# Sheet1.net
KiCad netlist of a schematic drawn in Altium Designer
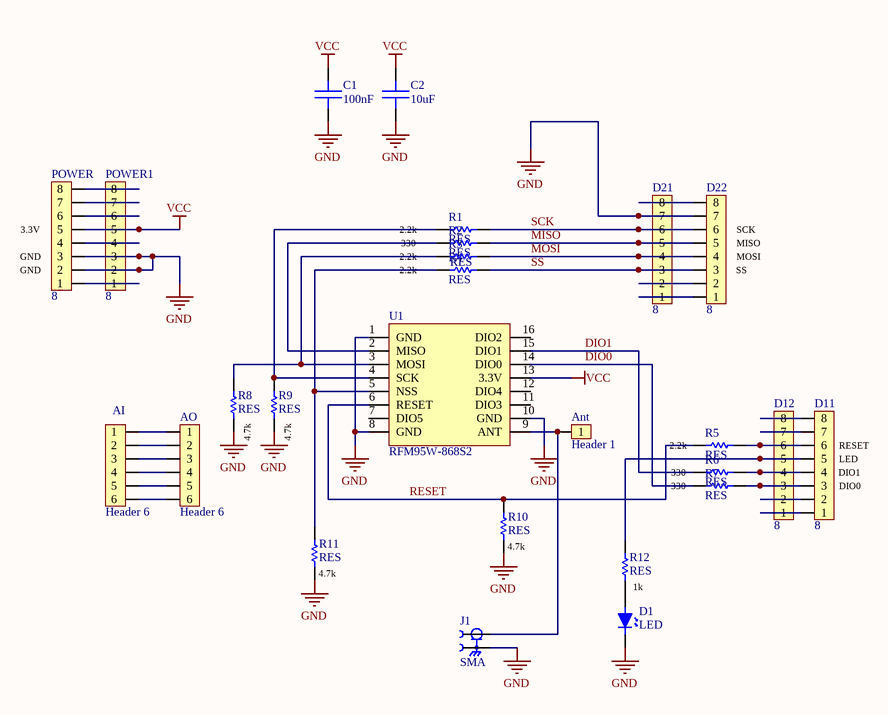
[diagram p0: Sheet1.SchDoc]

(export (version "E")
  (design (tool "Eeschema 10.0.6"))
  (components
    (comp (ref "AI")
      (value "Header 6")
      (footprint "PH-1X6")
      (description "PIN HEADER 1x6 2.56mm")
      (libsource (lib "") (part "PH-1X6_1"))
    )
    (comp (ref "Ant")
      (value "Header 1")
      (footprint "PH-1X1")
      (description "PIN HEADER 1x1 2.56mm")
      (libsource (lib "IOElectro") (part "PH-1X1"))
    )
    (comp (ref "AO")
      (value "Header 6")
      (footprint "PH-1X6")
      (description "PIN HEADER 1x6 2.56mm")
      (libsource (lib "IOElectro") (part "PH-1X6"))
    )
    (comp (ref "C1")
      (value "100nF")
      (footprint "C-0805")
      (description "CAPACITOR BIPOLAR")
      (libsource (lib "IOElectro") (part "CAP"))
    )
    (comp (ref "C2")
      (value "10uF")
      (footprint "C-0805")
      (description "CAPACITOR BIPOLAR")
      (libsource (lib "IOElectro") (part "CAP"))
    )
    (comp (ref "D1") (value "LED") (footprint "LED-0805") (libsource (lib "IOElectro") (part "LED")))
    (comp (ref "D11")
      (value "8")
      (footprint "PH-1X8")
      (description "PIN HEADER 1x8 2.56mm")
      (libsource (lib "IOElectro") (part "PH-1X8"))
    )
    (comp (ref "D12")
      (value "8")
      (footprint "PH-1X8")
      (description "PIN HEADER 1x8 2.56mm")
      (libsource (lib "IOElectro") (part "PH-1X8"))
    )
    (comp (ref "D21")
      (value "8")
      (footprint "PH-1X8")
      (description "PIN HEADER 1x8 2.56mm")
      (libsource (lib "IOElectro") (part "PH-1X8"))
    )
    (comp (ref "D22")
      (value "8")
      (footprint "PH-1X8")
      (description "PIN HEADER 1x8 2.56mm")
      (libsource (lib "IOElectro") (part "PH-1X8"))
    )
    (comp (ref "J1")
      (value "SMA")
      (footprint "SMA-CONNECTOR-R")
      (description "Straight SMA Connector")
      (fields (field (name "MP") "altium_native_batch"))
      (libsource (lib "IOElectro") (part "SMA-CONNECTOR"))
    )
    (comp (ref "POWER")
      (value "8")
      (footprint "PH-1X8")
      (description "PIN HEADER 1x8 2.56mm")
      (libsource (lib "") (part "PH-1X8_1"))
    )
    (comp (ref "POWER1")
      (value "8")
      (footprint "PH-1X8")
      (description "PIN HEADER 1x8 2.56mm")
      (libsource (lib "") (part "PH-1X8_1"))
    )
    (comp (ref "R1") (value "RES") (footprint "R-0805") (libsource (lib "IOElectro") (part "RES")))
    (comp (ref "R2") (value "RES") (footprint "R-0805") (libsource (lib "IOElectro") (part "RES")))
    (comp (ref "R3") (value "RES") (footprint "R-0805") (libsource (lib "IOElectro") (part "RES")))
    (comp (ref "R4") (value "RES") (footprint "R-0805") (libsource (lib "IOElectro") (part "RES")))
    (comp (ref "R5") (value "RES") (footprint "R-0805") (libsource (lib "IOElectro") (part "RES")))
    (comp (ref "R6") (value "RES") (footprint "R-0805") (libsource (lib "IOElectro") (part "RES")))
    (comp (ref "R7") (value "RES") (footprint "R-0805") (libsource (lib "IOElectro") (part "RES")))
    (comp (ref "R8") (value "RES") (footprint "R-0805") (libsource (lib "IOElectro") (part "RES")))
    (comp (ref "R9") (value "RES") (footprint "R-0805") (libsource (lib "IOElectro") (part "RES")))
    (comp (ref "R10") (value "RES") (footprint "R-0805") (libsource (lib "IOElectro") (part "RES")))
    (comp (ref "R11") (value "RES") (footprint "R-0805") (libsource (lib "IOElectro") (part "RES")))
    (comp (ref "R12") (value "RES") (footprint "R-0805") (libsource (lib "IOElectro") (part "RES")))
    (comp (ref "U1")
      (value "RFM95W-868S2")
      (footprint "RFM95")
      (description "Transceiver RF 868 MHz (+20/-139dBm), FSK, GFSK, MSK, GMSK, LoRaTM, OOK, 16 x 16 mm")
      (fields (field (name "MANUFACTURER") "RF Solutions"))
      (libsource (lib "IOElectro") (part "RFM95W-868S2"))
    )
  )
  (nets
    (net (code "1") (name "/DIO0") (class "Default")
      (node (ref "R7") (pin "1") (pinfunction "1_1") (pintype "passive"))
      (node (ref "U1") (pin "14") (pinfunction "DIO0_14") (pintype "passive"))
    )
    (net (code "2") (name "/DIO1") (class "Default")
      (node (ref "R6") (pin "1") (pinfunction "1_1") (pintype "passive"))
      (node (ref "U1") (pin "15") (pinfunction "DIO1_15") (pintype "passive"))
    )
    (net (code "3") (name "/MISO") (class "Default")
      (node (ref "D21") (pin "5") (pinfunction "5_5") (pintype "passive"))
      (node (ref "D22") (pin "5") (pinfunction "5_5") (pintype "passive"))
      (node (ref "R2") (pin "2") (pinfunction "2_2") (pintype "passive"))
    )
    (net (code "4") (name "/MOSI") (class "Default")
      (node (ref "D21") (pin "4") (pinfunction "4_4") (pintype "passive"))
      (node (ref "D22") (pin "4") (pinfunction "4_4") (pintype "passive"))
      (node (ref "R3") (pin "2") (pinfunction "2_2") (pintype "passive"))
    )
    (net (code "5") (name "/RESET") (class "Default")
      (node (ref "R10") (pin "2") (pinfunction "2_2") (pintype "passive"))
      (node (ref "R5") (pin "1") (pinfunction "1_1") (pintype "passive"))
      (node (ref "U1") (pin "6") (pinfunction "RESET_6") (pintype "passive"))
    )
    (net (code "6") (name "/SCK") (class "Default")
      (node (ref "D21") (pin "6") (pinfunction "6_6") (pintype "passive"))
      (node (ref "D22") (pin "6") (pinfunction "6_6") (pintype "passive"))
      (node (ref "R1") (pin "2") (pinfunction "2_2") (pintype "passive"))
    )
    (net (code "7") (name "/SS") (class "Default")
      (node (ref "D21") (pin "3") (pinfunction "3_3") (pintype "passive"))
      (node (ref "D22") (pin "3") (pinfunction "3_3") (pintype "passive"))
      (node (ref "R4") (pin "2") (pinfunction "2_2") (pintype "passive"))
    )
    (net (code "8") (name "GND") (class "Default")
      (node (ref "C1") (pin "2") (pinfunction "2_2") (pintype "passive"))
      (node (ref "C2") (pin "2") (pinfunction "2_2") (pintype "passive"))
      (node (ref "D1") (pin "K") (pinfunction "K_K") (pintype "passive"))
      (node (ref "D21") (pin "7") (pinfunction "7_7") (pintype "passive"))
      (node (ref "D22") (pin "7") (pinfunction "7_7") (pintype "passive"))
      (node (ref "J1") (pin "2") (pinfunction "2_2") (pintype "passive"))
      (node (ref "POWER") (pin "2") (pinfunction "2_2") (pintype "passive"))
      (node (ref "POWER") (pin "3") (pinfunction "3_3") (pintype "passive"))
      (node (ref "POWER1") (pin "2") (pinfunction "2_2") (pintype "passive"))
      (node (ref "POWER1") (pin "3") (pinfunction "3_3") (pintype "passive"))
      (node (ref "R10") (pin "1") (pinfunction "1_1") (pintype "passive"))
      (node (ref "R11") (pin "1") (pinfunction "1_1") (pintype "passive"))
      (node (ref "R8") (pin "1") (pinfunction "1_1") (pintype "passive"))
      (node (ref "R9") (pin "1") (pinfunction "1_1") (pintype "passive"))
      (node (ref "U1") (pin "1") (pinfunction "GND_1") (pintype "passive"))
      (node (ref "U1") (pin "10") (pinfunction "GND_10") (pintype "passive"))
      (node (ref "U1") (pin "8") (pinfunction "GND_8") (pintype "passive"))
    )
    (net (code "9") (name "Net-(AI-Pad1)") (class "Default")
      (node (ref "AI") (pin "1") (pinfunction "1_1") (pintype "passive"))
      (node (ref "AO") (pin "1") (pinfunction "1_1") (pintype "passive"))
    )
    (net (code "10") (name "Net-(AI-Pad2)") (class "Default")
      (node (ref "AI") (pin "2") (pinfunction "2_2") (pintype "passive"))
      (node (ref "AO") (pin "2") (pinfunction "2_2") (pintype "passive"))
    )
    (net (code "11") (name "Net-(AI-Pad3)") (class "Default")
      (node (ref "AI") (pin "3") (pinfunction "3_3") (pintype "passive"))
      (node (ref "AO") (pin "3") (pinfunction "3_3") (pintype "passive"))
    )
    (net (code "12") (name "Net-(AI-Pad4)") (class "Default")
      (node (ref "AI") (pin "4") (pinfunction "4_4") (pintype "passive"))
      (node (ref "AO") (pin "4") (pinfunction "4_4") (pintype "passive"))
    )
    (net (code "13") (name "Net-(AI-Pad5)") (class "Default")
      (node (ref "AI") (pin "5") (pinfunction "5_5") (pintype "passive"))
      (node (ref "AO") (pin "5") (pinfunction "5_5") (pintype "passive"))
    )
    (net (code "14") (name "Net-(AI-Pad6)") (class "Default")
      (node (ref "AI") (pin "6") (pinfunction "6_6") (pintype "passive"))
      (node (ref "AO") (pin "6") (pinfunction "6_6") (pintype "passive"))
    )
    (net (code "15") (name "Net-(D1-PadA)") (class "Default")
      (node (ref "D1") (pin "A") (pinfunction "A_A") (pintype "passive"))
      (node (ref "R12") (pin "1") (pinfunction "1_1") (pintype "passive"))
    )
    (net (code "16") (name "Net-(D11-Pad1)") (class "Default")
      (node (ref "D11") (pin "1") (pinfunction "1_1") (pintype "passive"))
      (node (ref "D12") (pin "1") (pinfunction "1_1") (pintype "passive"))
    )
    (net (code "17") (name "Net-(D11-Pad2)") (class "Default")
      (node (ref "D11") (pin "2") (pinfunction "2_2") (pintype "passive"))
      (node (ref "D12") (pin "2") (pinfunction "2_2") (pintype "passive"))
    )
    (net (code "18") (name "Net-(D11-Pad3)") (class "Default")
      (node (ref "D11") (pin "3") (pinfunction "3_3") (pintype "passive"))
      (node (ref "D12") (pin "3") (pinfunction "3_3") (pintype "passive"))
      (node (ref "R7") (pin "2") (pinfunction "2_2") (pintype "passive"))
    )
    (net (code "19") (name "Net-(D11-Pad4)") (class "Default")
      (node (ref "D11") (pin "4") (pinfunction "4_4") (pintype "passive"))
      (node (ref "D12") (pin "4") (pinfunction "4_4") (pintype "passive"))
      (node (ref "R6") (pin "2") (pinfunction "2_2") (pintype "passive"))
    )
    (net (code "20") (name "Net-(D11-Pad5)") (class "Default")
      (node (ref "D11") (pin "5") (pinfunction "5_5") (pintype "passive"))
      (node (ref "D12") (pin "5") (pinfunction "5_5") (pintype "passive"))
      (node (ref "R12") (pin "2") (pinfunction "2_2") (pintype "passive"))
    )
    (net (code "21") (name "Net-(D11-Pad6)") (class "Default")
      (node (ref "D11") (pin "6") (pinfunction "6_6") (pintype "passive"))
      (node (ref "D12") (pin "6") (pinfunction "6_6") (pintype "passive"))
      (node (ref "R5") (pin "2") (pinfunction "2_2") (pintype "passive"))
    )
    (net (code "22") (name "Net-(D11-Pad7)") (class "Default")
      (node (ref "D11") (pin "7") (pinfunction "7_7") (pintype "passive"))
      (node (ref "D12") (pin "7") (pinfunction "7_7") (pintype "passive"))
    )
    (net (code "23") (name "Net-(D11-Pad8)") (class "Default")
      (node (ref "D11") (pin "8") (pinfunction "8_8") (pintype "passive"))
      (node (ref "D12") (pin "8") (pinfunction "8_8") (pintype "passive"))
    )
    (net (code "24") (name "Net-(D21-Pad1)") (class "Default")
      (node (ref "D21") (pin "1") (pinfunction "1_1") (pintype "passive"))
      (node (ref "D22") (pin "1") (pinfunction "1_1") (pintype "passive"))
    )
    (net (code "25") (name "Net-(D21-Pad2)") (class "Default")
      (node (ref "D21") (pin "2") (pinfunction "2_2") (pintype "passive"))
      (node (ref "D22") (pin "2") (pinfunction "2_2") (pintype "passive"))
    )
    (net (code "26") (name "Net-(D21-Pad8)") (class "Default")
      (node (ref "D21") (pin "8") (pinfunction "8_8") (pintype "passive"))
      (node (ref "D22") (pin "8") (pinfunction "8_8") (pintype "passive"))
    )
    (net (code "27") (name "Net-(POWER-Pad1)") (class "Default")
      (node (ref "POWER") (pin "1") (pinfunction "1_1") (pintype "passive"))
      (node (ref "POWER1") (pin "1") (pinfunction "1_1") (pintype "passive"))
    )
    (net (code "28") (name "Net-(POWER-Pad4)") (class "Default")
      (node (ref "POWER") (pin "4") (pinfunction "4_4") (pintype "passive"))
      (node (ref "POWER1") (pin "4") (pinfunction "4_4") (pintype "passive"))
    )
    (net (code "29") (name "Net-(POWER-Pad6)") (class "Default")
      (node (ref "POWER") (pin "6") (pinfunction "6_6") (pintype "passive"))
      (node (ref "POWER1") (pin "6") (pinfunction "6_6") (pintype "passive"))
    )
    (net (code "30") (name "Net-(POWER-Pad7)") (class "Default")
      (node (ref "POWER") (pin "7") (pinfunction "7_7") (pintype "passive"))
      (node (ref "POWER1") (pin "7") (pinfunction "7_7") (pintype "passive"))
    )
    (net (code "31") (name "Net-(POWER-Pad8)") (class "Default")
      (node (ref "POWER") (pin "8") (pinfunction "8_8") (pintype "passive"))
      (node (ref "POWER1") (pin "8") (pinfunction "8_8") (pintype "passive"))
    )
    (net (code "32") (name "Net-(U1-ANT)") (class "Default")
      (node (ref "Ant") (pin "1") (pinfunction "1_1") (pintype "passive"))
      (node (ref "J1") (pin "1") (pinfunction "1_1") (pintype "passive"))
      (node (ref "U1") (pin "9") (pinfunction "ANT_9") (pintype "passive"))
    )
    (net (code "33") (name "Net-(U1-MISO)") (class "Default")
      (node (ref "R2") (pin "1") (pinfunction "1_1") (pintype "passive"))
      (node (ref "U1") (pin "2") (pinfunction "MISO_2") (pintype "passive"))
    )
    (net (code "34") (name "Net-(U1-MOSI)") (class "Default")
      (node (ref "R3") (pin "1") (pinfunction "1_1") (pintype "passive"))
      (node (ref "R8") (pin "2") (pinfunction "2_2") (pintype "passive"))
      (node (ref "U1") (pin "3") (pinfunction "MOSI_3") (pintype "passive"))
    )
    (net (code "35") (name "Net-(U1-NSS)") (class "Default")
      (node (ref "R11") (pin "2") (pinfunction "2_2") (pintype "passive"))
      (node (ref "R4") (pin "1") (pinfunction "1_1") (pintype "passive"))
      (node (ref "U1") (pin "5") (pinfunction "NSS_5") (pintype "passive"))
    )
    (net (code "36") (name "Net-(U1-SCK)") (class "Default")
      (node (ref "R1") (pin "1") (pinfunction "1_1") (pintype "passive"))
      (node (ref "R9") (pin "2") (pinfunction "2_2") (pintype "passive"))
      (node (ref "U1") (pin "4") (pinfunction "SCK_4") (pintype "passive"))
    )
    (net (code "37") (name "VCC") (class "Default")
      (node (ref "C1") (pin "1") (pinfunction "1_1") (pintype "passive"))
      (node (ref "C2") (pin "1") (pinfunction "1_1") (pintype "passive"))
      (node (ref "POWER") (pin "5") (pinfunction "5_5") (pintype "passive"))
      (node (ref "POWER1") (pin "5") (pinfunction "5_5") (pintype "passive"))
      (node (ref "U1") (pin "13") (pinfunction "3.3V_13") (pintype "passive"))
    )
    (net (code "38") (name "unconnected-(U1-DIO2-Pad16)") (class "Default")
      (node (ref "U1") (pin "16") (pinfunction "DIO2_16") (pintype "passive"))
    )
    (net (code "39") (name "unconnected-(U1-DIO3-Pad11)") (class "Default")
      (node (ref "U1") (pin "11") (pinfunction "DIO3_11") (pintype "passive"))
    )
    (net (code "40") (name "unconnected-(U1-DIO4-Pad12)") (class "Default")
      (node (ref "U1") (pin "12") (pinfunction "DIO4_12") (pintype "passive"))
    )
    (net (code "41") (name "unconnected-(U1-DIO5-Pad7)") (class "Default")
      (node (ref "U1") (pin "7") (pinfunction "DIO5_7") (pintype "passive"))
    )
  )
)
